# TopLevel.net
KiCad netlist of a schematic drawn in Altium Designer
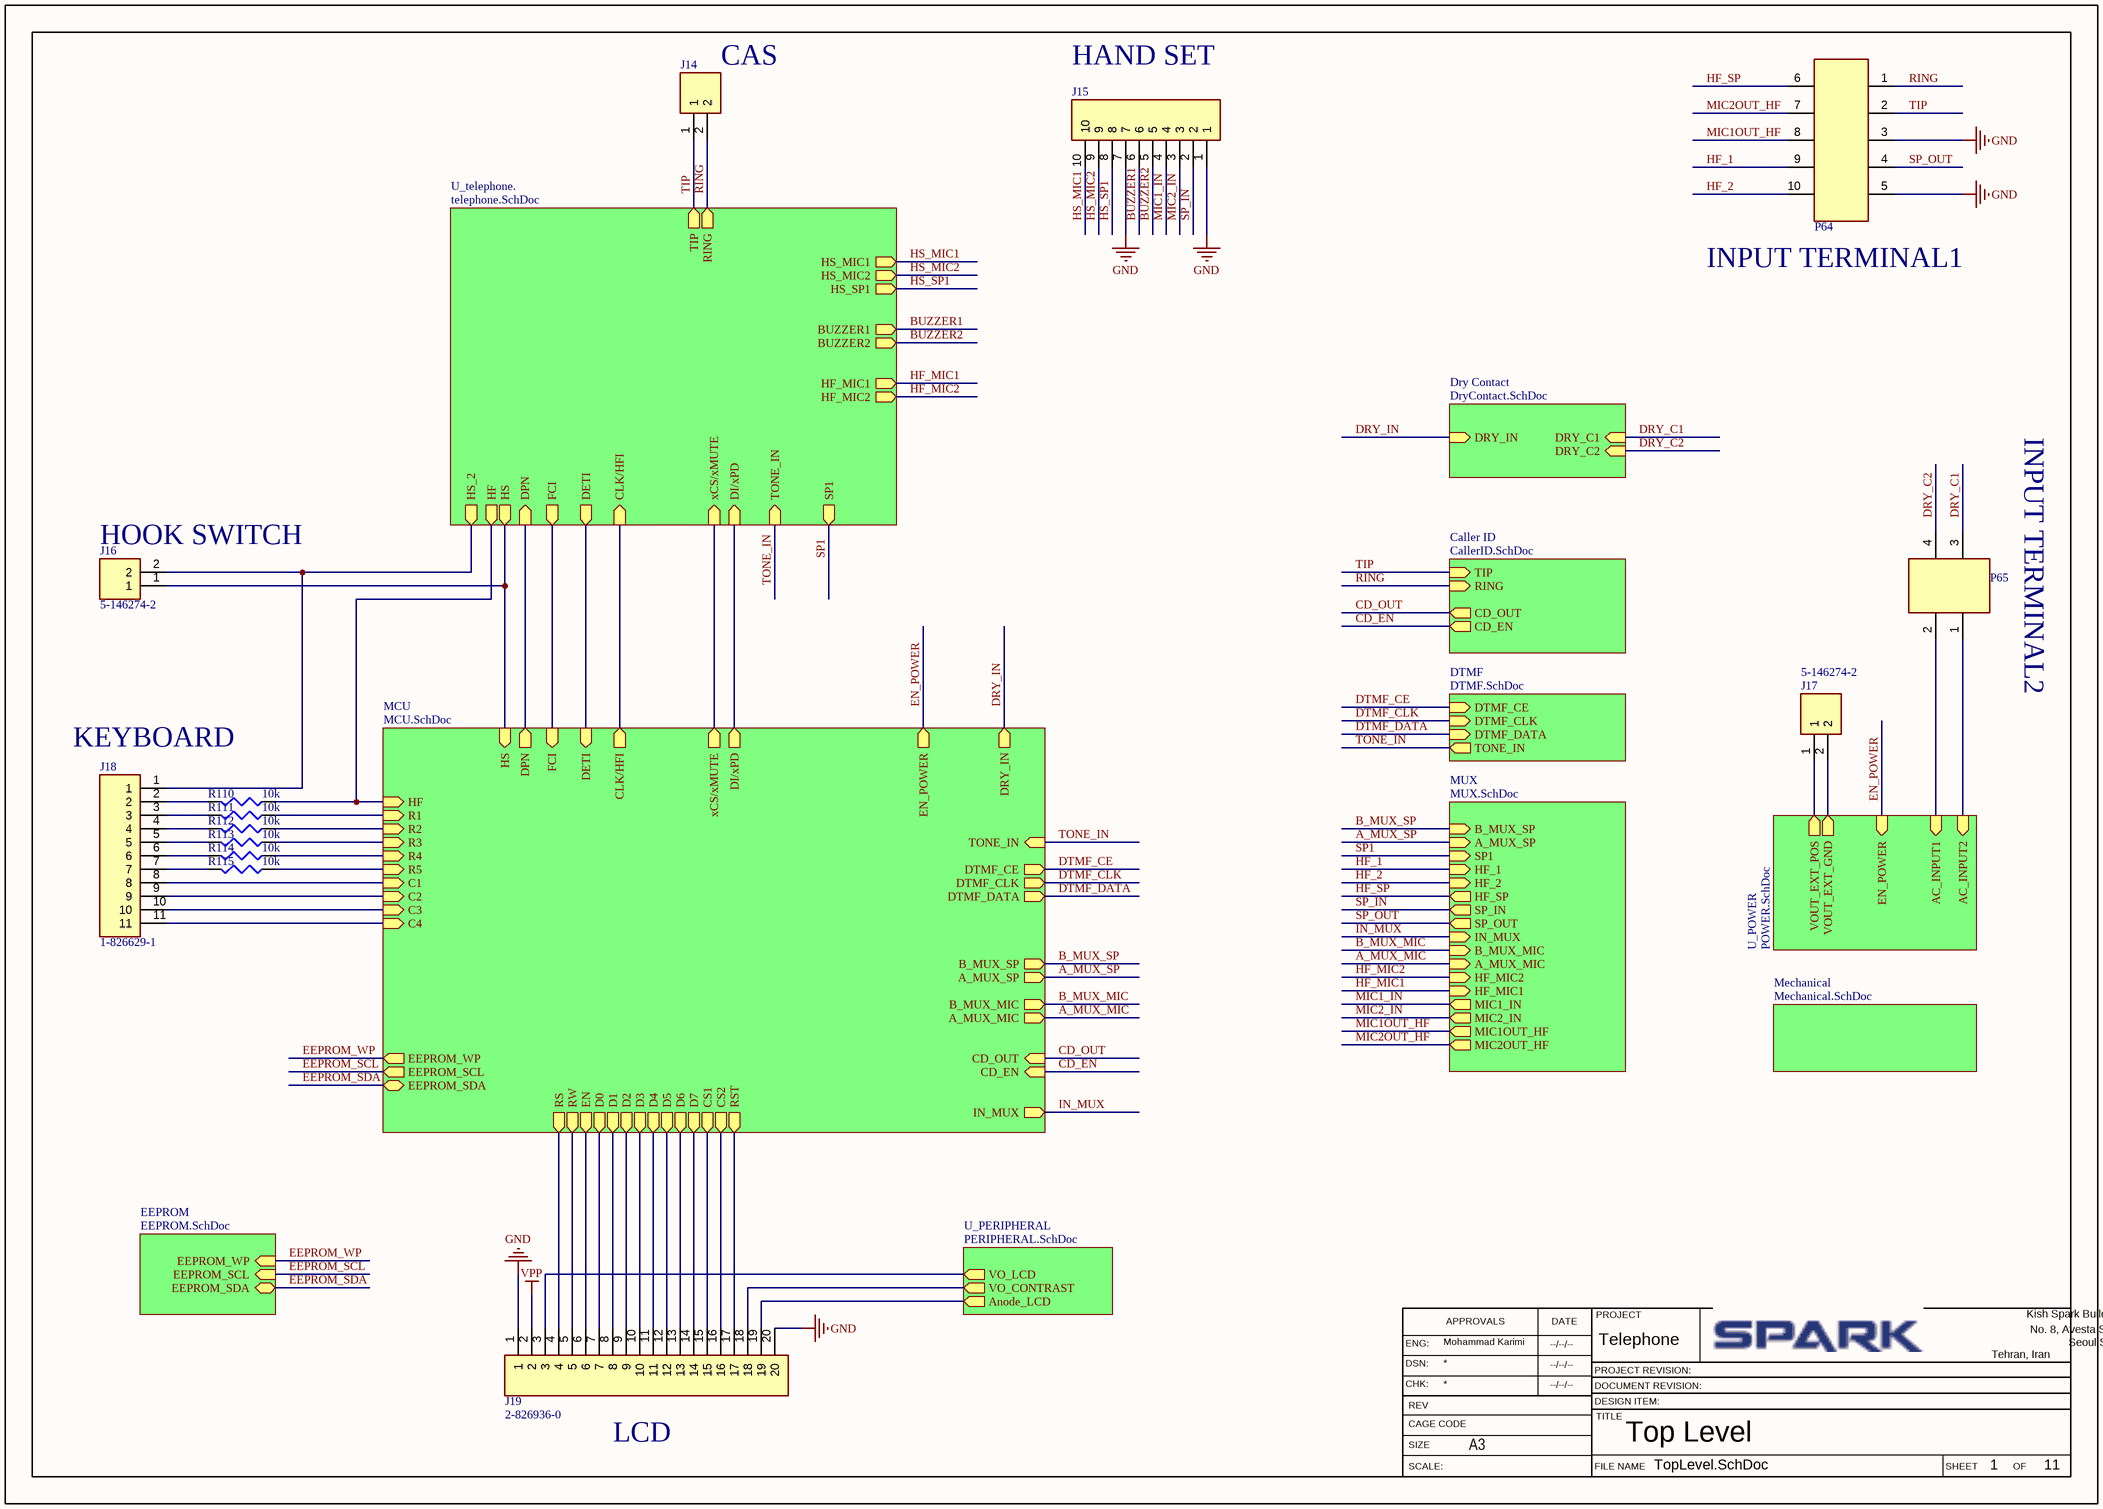
[diagram p0: TopLevel.SchDoc]

(export (version "E")
  (design (tool "Eeschema 10.0.6"))
  (components
    (comp (ref "J14")
      (value "5-146274-2")
      (footprint "TE_5-146274-2")
      (description "Conn Unshrouded Header HDR 2 POS 2.54mm Solder ST Top Entry Thru-Hole Carton")
      (libsource (lib "Kish Spark") (part "5-146274-2"))
    )
    (comp (ref "J15")
      (value "146443-5")
      (footprint "146443-5")
      (description "Conn Unshrouded Header HDR 10 POS 2.54mm Solder ST Thru-Hole Carton")
      (libsource (lib "Kish Spark") (part "146443-5"))
    )
    (comp (ref "J16")
      (value "5-146274-2")
      (footprint "TE_5-146274-2")
      (description "Conn Unshrouded Header HDR 2 POS 2.54mm Solder ST Top Entry Thru-Hole Carton")
      (libsource (lib "") (part "5-146274-2_1"))
    )
    (comp (ref "J17")
      (value "5-146274-2")
      (footprint "TE_5-146274-2")
      (description "Conn Unshrouded Header HDR 2 POS 2.54mm Solder ST Top Entry Thru-Hole Carton")
      (libsource (lib "Kish Spark") (part "5-146274-2"))
    )
    (comp (ref "J18")
      (value "1-826629-1")
      (footprint "1-826629-1")
      (description "Conn Unshrouded Header HDR 11 POS 2.54mm Solder ST Thru-Hole Carton")
      (libsource (lib "Kish Spark") (part "1-826629-1"))
    )
    (comp (ref "J19")
      (value "2-826936-0")
      (footprint "2-826936-0")
      (description "Conn Unshrouded Header HDR 20 POS 2.54mm Solder ST Thru-Hole Box")
      (libsource (lib "Kish Spark") (part "2-826936-0"))
    )
    (comp (ref "P64")
      (value "66201021122")
      (footprint "POWER 10 PIN")
      (description "WR-MPC3; 3mm Pitch 10 Way 2 Row Shrouded Straight PCB Header; Through Hole")
      (fields (field (name "MANUFACTURER") "Wurth Electronics"))
      (libsource (lib "Kish Spark") (part "66201021122"))
    )
    (comp (ref "P65")
      (value "66200421122")
      (footprint "power-4pin")
      (description "WR-MPC3 Series; 3mm Pitch 4 Way 2 Row Shrouded Straight PCB Header; Through Hole")
      (fields (field (name "MANUFACTURER") "Wurth Electronics"))
      (libsource (lib "Kish Spark") (part "66200421122"))
    )
    (comp (ref "R110")
      (value "10k")
      (footprint "R0603")
      (description "Res Thick Film 0603 10K Ohm 5% 1/10W 200ppm/C Molded SMD SMD Paper T/R")
      (fields
        (field (name "TOLERANCE") "5%")
        (field (name "Comment") "CRCW060310K0JNEA")
        (field (name "SOURCE") "PTZLib.SchLib")
      )
      (libsource (lib "Kish Spark") (part "RN73R1JTTD3302F10"))
    )
    (comp (ref "R111")
      (value "10k")
      (footprint "R0603")
      (description "Res Thick Film 0603 10K Ohm 5% 1/10W 200ppm/C Molded SMD SMD Paper T/R")
      (fields
        (field (name "TOLERANCE") "5%")
        (field (name "Comment") "CRCW060310K0JNEA")
        (field (name "SOURCE") "PTZLib.SchLib")
      )
      (libsource (lib "Kish Spark") (part "RN73R1JTTD3302F10"))
    )
    (comp (ref "R112")
      (value "10k")
      (footprint "R0603")
      (description "Res Thick Film 0603 10K Ohm 5% 1/10W 200ppm/C Molded SMD SMD Paper T/R")
      (fields
        (field (name "TOLERANCE") "5%")
        (field (name "Comment") "CRCW060310K0JNEA")
        (field (name "SOURCE") "PTZLib.SchLib")
      )
      (libsource (lib "Kish Spark") (part "RN73R1JTTD3302F10"))
    )
    (comp (ref "R113")
      (value "10k")
      (footprint "R0603")
      (description "Res Thick Film 0603 10K Ohm 5% 1/10W 200ppm/C Molded SMD SMD Paper T/R")
      (fields
        (field (name "TOLERANCE") "5%")
        (field (name "Comment") "CRCW060310K0JNEA")
        (field (name "SOURCE") "PTZLib.SchLib")
      )
      (libsource (lib "Kish Spark") (part "RN73R1JTTD3302F10"))
    )
    (comp (ref "R114")
      (value "10k")
      (footprint "R0603")
      (description "Res Thick Film 0603 10K Ohm 5% 1/10W 200ppm/C Molded SMD SMD Paper T/R")
      (fields
        (field (name "TOLERANCE") "5%")
        (field (name "Comment") "CRCW060310K0JNEA")
        (field (name "SOURCE") "PTZLib.SchLib")
      )
      (libsource (lib "Kish Spark") (part "RN73R1JTTD3302F10"))
    )
    (comp (ref "R115")
      (value "10k")
      (footprint "R0603")
      (description "Res Thick Film 0603 10K Ohm 5% 1/10W 200ppm/C Molded SMD SMD Paper T/R")
      (fields
        (field (name "TOLERANCE") "5%")
        (field (name "Comment") "CRCW060310K0JNEA")
        (field (name "SOURCE") "PTZLib.SchLib")
      )
      (libsource (lib "Kish Spark") (part "RN73R1JTTD3302F10"))
    )
  )
  (nets
    (net (code "1") (name "/AC_INPUT1") (class "Default")
      (node (ref "P65") (pin "2") (pinfunction "2_2") (pintype "passive"))
    )
    (net (code "2") (name "/AC_INPUT2") (class "Default")
      (node (ref "P65") (pin "1") (pinfunction "1_1") (pintype "passive"))
    )
    (net (code "5") (name "/Anode_LCD") (class "Default")
      (node (ref "J19") (pin "19") (pinfunction "19_19") (pintype "passive"))
    )
    (net (code "6") (name "/BUZZER1") (class "Default")
      (node (ref "J15") (pin "6") (pinfunction "6_6") (pintype "passive"))
    )
    (net (code "7") (name "/BUZZER2") (class "Default")
      (node (ref "J15") (pin "5") (pinfunction "5_5") (pintype "passive"))
    )
    (net (code "10") (name "/C1") (class "Default")
      (node (ref "J18") (pin "8") (pinfunction "8_8") (pintype "passive"))
    )
    (net (code "11") (name "/C2") (class "Default")
      (node (ref "J18") (pin "9") (pinfunction "9_9") (pintype "passive"))
    )
    (net (code "12") (name "/C3") (class "Default")
      (node (ref "J18") (pin "10") (pinfunction "10_10") (pintype "passive"))
    )
    (net (code "13") (name "/C4") (class "Default")
      (node (ref "J18") (pin "11") (pinfunction "11_11") (pintype "passive"))
    )
    (net (code "17") (name "/CS1") (class "Default")
      (node (ref "J19") (pin "15") (pinfunction "15_15") (pintype "passive"))
    )
    (net (code "18") (name "/CS2") (class "Default")
      (node (ref "J19") (pin "16") (pinfunction "16_16") (pintype "passive"))
    )
    (net (code "19") (name "/D0") (class "Default")
      (node (ref "J19") (pin "7") (pinfunction "7_7") (pintype "passive"))
    )
    (net (code "20") (name "/D1") (class "Default")
      (node (ref "J19") (pin "8") (pinfunction "8_8") (pintype "passive"))
    )
    (net (code "21") (name "/D2") (class "Default")
      (node (ref "J19") (pin "9") (pinfunction "9_9") (pintype "passive"))
    )
    (net (code "22") (name "/D3") (class "Default")
      (node (ref "J19") (pin "10") (pinfunction "10_10") (pintype "passive"))
    )
    (net (code "23") (name "/D4") (class "Default")
      (node (ref "J19") (pin "11") (pinfunction "11_11") (pintype "passive"))
    )
    (net (code "24") (name "/D5") (class "Default")
      (node (ref "J19") (pin "12") (pinfunction "12_12") (pintype "passive"))
    )
    (net (code "25") (name "/D6") (class "Default")
      (node (ref "J19") (pin "13") (pinfunction "13_13") (pintype "passive"))
    )
    (net (code "26") (name "/D7") (class "Default")
      (node (ref "J19") (pin "14") (pinfunction "14_14") (pintype "passive"))
    )
    (net (code "30") (name "/DRY_C1") (class "Default")
      (node (ref "P65") (pin "3") (pinfunction "3_3") (pintype "passive"))
    )
    (net (code "31") (name "/DRY_C2") (class "Default")
      (node (ref "P65") (pin "4") (pinfunction "4_4") (pintype "passive"))
    )
    (net (code "39") (name "/EN") (class "Default")
      (node (ref "J19") (pin "6") (pinfunction "6_6") (pintype "passive"))
    )
    (net (code "42") (name "/HF") (class "Default")
      (node (ref "R110") (pin "1") (pinfunction "1_1") (pintype "passive"))
    )
    (net (code "43") (name "/HF_1") (class "Default")
      (node (ref "P64") (pin "9") (pinfunction "9_9") (pintype "passive"))
    )
    (net (code "44") (name "/HF_2") (class "Default")
      (node (ref "P64") (pin "10") (pinfunction "10_10") (pintype "passive"))
    )
    (net (code "47") (name "/HF_SP") (class "Default")
      (node (ref "P64") (pin "6") (pinfunction "6_6") (pintype "passive"))
    )
    (net (code "48") (name "/HS") (class "Default")
      (node (ref "J16") (pin "1") (pinfunction "1_1") (pintype "passive"))
    )
    (net (code "49") (name "/HS_2") (class "Default")
      (node (ref "J16") (pin "2") (pinfunction "2_2") (pintype "passive"))
      (node (ref "J18") (pin "1") (pinfunction "1_1") (pintype "passive"))
    )
    (net (code "50") (name "/HS_MIC1") (class "Default")
      (node (ref "J15") (pin "10") (pinfunction "10_10") (pintype "passive"))
    )
    (net (code "51") (name "/HS_MIC2") (class "Default")
      (node (ref "J15") (pin "9") (pinfunction "9_9") (pintype "passive"))
    )
    (net (code "52") (name "/HS_SP1") (class "Default")
      (node (ref "J15") (pin "8") (pinfunction "8_8") (pintype "passive"))
    )
    (net (code "54") (name "/MIC1OUT_HF") (class "Default")
      (node (ref "P64") (pin "8") (pinfunction "8_8") (pintype "passive"))
    )
    (net (code "55") (name "/MIC1_IN") (class "Default")
      (node (ref "J15") (pin "4") (pinfunction "4_4") (pintype "passive"))
    )
    (net (code "56") (name "/MIC2OUT_HF") (class "Default")
      (node (ref "P64") (pin "7") (pinfunction "7_7") (pintype "passive"))
    )
    (net (code "57") (name "/MIC2_IN") (class "Default")
      (node (ref "J15") (pin "3") (pinfunction "3_3") (pintype "passive"))
    )
    (net (code "58") (name "/R1") (class "Default")
      (node (ref "R111") (pin "1") (pinfunction "1_1") (pintype "passive"))
    )
    (net (code "59") (name "/R2") (class "Default")
      (node (ref "R112") (pin "1") (pinfunction "1_1") (pintype "passive"))
    )
    (net (code "60") (name "/R3") (class "Default")
      (node (ref "R113") (pin "1") (pinfunction "1_1") (pintype "passive"))
    )
    (net (code "61") (name "/R4") (class "Default")
      (node (ref "R114") (pin "1") (pinfunction "1_1") (pintype "passive"))
    )
    (net (code "62") (name "/R5") (class "Default")
      (node (ref "R115") (pin "1") (pinfunction "1_1") (pintype "passive"))
    )
    (net (code "63") (name "/RING") (class "Default")
      (node (ref "J14") (pin "2") (pinfunction "2_2") (pintype "passive"))
      (node (ref "P64") (pin "1") (pinfunction "1_1") (pintype "passive"))
    )
    (net (code "64") (name "/RS") (class "Default")
      (node (ref "J19") (pin "4") (pinfunction "4_4") (pintype "passive"))
    )
    (net (code "65") (name "/RST") (class "Default")
      (node (ref "J19") (pin "17") (pinfunction "17_17") (pintype "passive"))
    )
    (net (code "66") (name "/RW") (class "Default")
      (node (ref "J19") (pin "5") (pinfunction "5_5") (pintype "passive"))
    )
    (net (code "68") (name "/SP_IN") (class "Default")
      (node (ref "J15") (pin "2") (pinfunction "2_2") (pintype "passive"))
    )
    (net (code "69") (name "/SP_OUT") (class "Default")
      (node (ref "P64") (pin "4") (pinfunction "4_4") (pintype "passive"))
    )
    (net (code "70") (name "/TIP") (class "Default")
      (node (ref "J14") (pin "1") (pinfunction "1_1") (pintype "passive"))
      (node (ref "P64") (pin "2") (pinfunction "2_2") (pintype "passive"))
    )
    (net (code "72") (name "/VOUT_EXT_GND") (class "Default")
      (node (ref "J17") (pin "2") (pinfunction "2_2") (pintype "passive"))
    )
    (net (code "73") (name "/VOUT_EXT_POS") (class "Default")
      (node (ref "J17") (pin "1") (pinfunction "1_1") (pintype "passive"))
    )
    (net (code "74") (name "/VO_CONTRAST") (class "Default")
      (node (ref "J19") (pin "18") (pinfunction "18_18") (pintype "passive"))
    )
    (net (code "75") (name "/VO_LCD") (class "Default")
      (node (ref "J19") (pin "3") (pinfunction "3_3") (pintype "passive"))
    )
    (net (code "77") (name "GND") (class "Default")
      (node (ref "J15") (pin "1") (pinfunction "1_1") (pintype "passive"))
      (node (ref "J15") (pin "7") (pinfunction "7_7") (pintype "passive"))
      (node (ref "J19") (pin "1") (pinfunction "1_1") (pintype "passive"))
      (node (ref "J19") (pin "20") (pinfunction "20_20") (pintype "passive"))
      (node (ref "P64") (pin "3") (pinfunction "3_3") (pintype "passive"))
      (node (ref "P64") (pin "5") (pinfunction "5_5") (pintype "passive"))
    )
    (net (code "78") (name "Net-(J18-Pad2)") (class "Default")
      (node (ref "J18") (pin "2") (pinfunction "2_2") (pintype "passive"))
      (node (ref "R110") (pin "2") (pinfunction "2_2") (pintype "passive"))
    )
    (net (code "79") (name "Net-(J18-Pad3)") (class "Default")
      (node (ref "J18") (pin "3") (pinfunction "3_3") (pintype "passive"))
      (node (ref "R111") (pin "2") (pinfunction "2_2") (pintype "passive"))
    )
    (net (code "80") (name "Net-(J18-Pad4)") (class "Default")
      (node (ref "J18") (pin "4") (pinfunction "4_4") (pintype "passive"))
      (node (ref "R112") (pin "2") (pinfunction "2_2") (pintype "passive"))
    )
    (net (code "81") (name "Net-(J18-Pad5)") (class "Default")
      (node (ref "J18") (pin "5") (pinfunction "5_5") (pintype "passive"))
      (node (ref "R113") (pin "2") (pinfunction "2_2") (pintype "passive"))
    )
    (net (code "82") (name "Net-(J18-Pad6)") (class "Default")
      (node (ref "J18") (pin "6") (pinfunction "6_6") (pintype "passive"))
      (node (ref "R114") (pin "2") (pinfunction "2_2") (pintype "passive"))
    )
    (net (code "83") (name "Net-(J18-Pad7)") (class "Default")
      (node (ref "J18") (pin "7") (pinfunction "7_7") (pintype "passive"))
      (node (ref "R115") (pin "2") (pinfunction "2_2") (pintype "passive"))
    )
    (net (code "84") (name "VPP") (class "Default")
      (node (ref "J19") (pin "2") (pinfunction "2_2") (pintype "passive"))
    )
  )
)
